# Medir-220-2.net
KiCad netlist of a schematic drawn in EAGLE
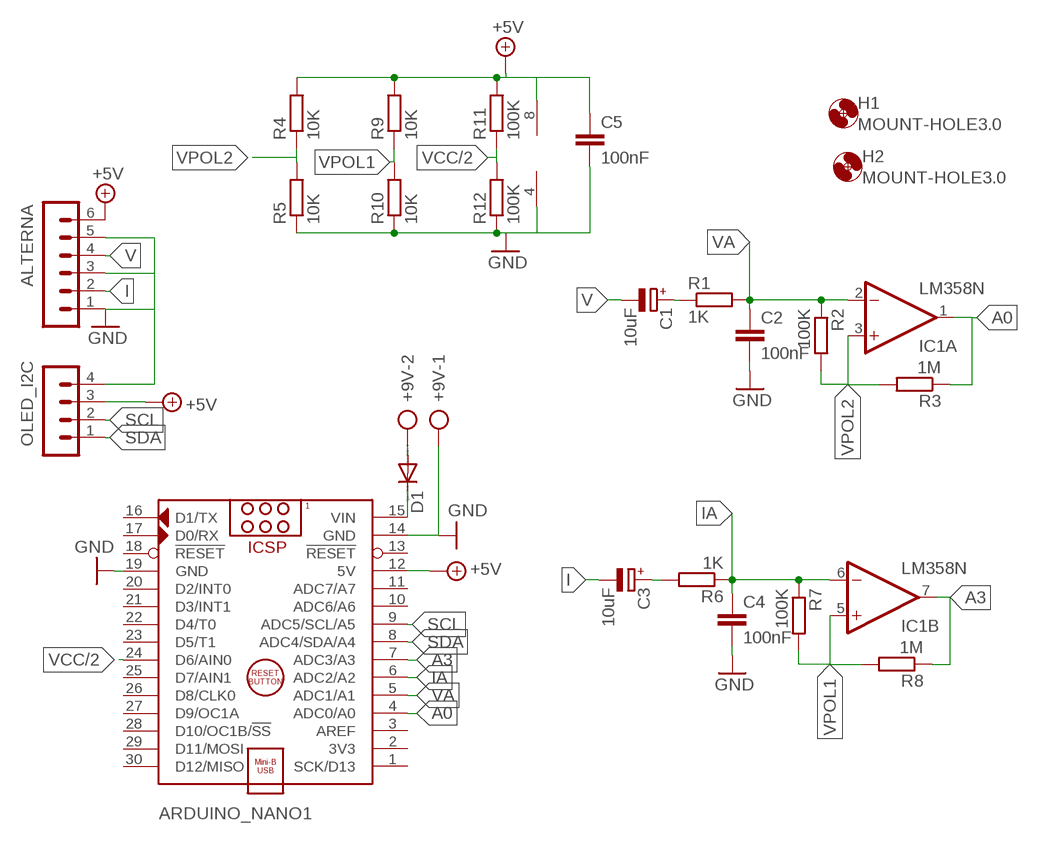
[diagram p0: schematic, sheet 1]

(export (version "E")
  (design (tool "Eeschema 10.0.6"))
  (components
    (comp (ref "+9V")
      (value "AK500/2")
      (footprint "eagle-import:AK500_2")
      (libsource (lib "eagle-import") (part "AK500/2"))
    )
    (comp (ref "ALTERNA")
      (value "MA06-1")
      (footprint "eagle-import:MA06-1")
      (libsource (lib "eagle-import") (part "MA06-1"))
    )
    (comp (ref "ARDUINO_NANO1")
      (value "ARDUINO_NANO")
      (footprint "eagle-import:ARDUINO_NANO")
      (libsource (lib "eagle-import") (part "ARDUINO_NANO"))
    )
    (comp (ref "C1")
      (value "10uF")
      (footprint "eagle-import:E2,5-5")
      (libsource (lib "eagle-import") (part "CPOL-EUE2.5-5"))
    )
    (comp (ref "C2")
      (value "100nF")
      (footprint "eagle-import:C050-025X075")
      (libsource (lib "eagle-import") (part "C-EU050-025X075"))
    )
    (comp (ref "C3")
      (value "10uF")
      (footprint "eagle-import:E2,5-5")
      (libsource (lib "eagle-import") (part "CPOL-EUE2.5-5"))
    )
    (comp (ref "C4")
      (value "100nF")
      (footprint "eagle-import:C050-025X075")
      (libsource (lib "eagle-import") (part "C-EU050-025X075"))
    )
    (comp (ref "C5")
      (value "100nF")
      (footprint "eagle-import:C025-025X050")
      (libsource (lib "eagle-import") (part "C-EU025-025X050"))
    )
    (comp (ref "D1")
      (value "DIODE-D-2.5")
      (footprint "eagle-import:D-2.5")
      (libsource (lib "eagle-import") (part "DIODE-D-2.5"))
    )
    (comp (ref "H1")
      (value "MOUNT-HOLE3.0")
      (footprint "eagle-import:3,0")
      (libsource (lib "eagle-import") (part "MOUNT-HOLE3.0"))
    )
    (comp (ref "H2")
      (value "MOUNT-HOLE3.0")
      (footprint "eagle-import:3,0")
      (libsource (lib "eagle-import") (part "MOUNT-HOLE3.0"))
    )
    (comp (ref "IC1")
      (value "LM358N")
      (footprint "eagle-import:DIL08")
      (libsource (lib "eagle-import") (part "LM358N"))
    )
    (comp (ref "OLED_I2C")
      (value "MA04-1")
      (footprint "eagle-import:MA04-1")
      (libsource (lib "eagle-import") (part "MA04-1"))
    )
    (comp (ref "R1")
      (value "1K")
      (footprint "eagle-import:0207_7")
      (libsource (lib "eagle-import") (part "R-EU_0207/7"))
    )
    (comp (ref "R2")
      (value "100K")
      (footprint "eagle-import:0207_7")
      (libsource (lib "eagle-import") (part "R-EU_0207/7"))
    )
    (comp (ref "R3")
      (value "1M")
      (footprint "eagle-import:0207_7")
      (libsource (lib "eagle-import") (part "R-EU_0207/7"))
    )
    (comp (ref "R4")
      (value "10K")
      (footprint "eagle-import:0207_10")
      (libsource (lib "eagle-import") (part "R-EU_0207/10"))
    )
    (comp (ref "R5")
      (value "10K")
      (footprint "eagle-import:0207_7")
      (libsource (lib "eagle-import") (part "R-EU_0207/7"))
    )
    (comp (ref "R6")
      (value "1K")
      (footprint "eagle-import:0207_7")
      (libsource (lib "eagle-import") (part "R-EU_0207/7"))
    )
    (comp (ref "R7")
      (value "100K")
      (footprint "eagle-import:0207_7")
      (libsource (lib "eagle-import") (part "R-EU_0207/7"))
    )
    (comp (ref "R8")
      (value "1M")
      (footprint "eagle-import:0207_7")
      (libsource (lib "eagle-import") (part "R-EU_0207/7"))
    )
    (comp (ref "R9")
      (value "10K")
      (footprint "eagle-import:0207_7")
      (libsource (lib "eagle-import") (part "R-EU_0207/7"))
    )
    (comp (ref "R10")
      (value "10K")
      (footprint "eagle-import:0207_7")
      (libsource (lib "eagle-import") (part "R-EU_0207/7"))
    )
    (comp (ref "R11")
      (value "100K")
      (footprint "eagle-import:0207_10")
      (libsource (lib "eagle-import") (part "R-EU_0207/10"))
    )
    (comp (ref "R12")
      (value "100K")
      (footprint "eagle-import:0207_10")
      (libsource (lib "eagle-import") (part "R-EU_0207/10"))
    )
  )
  (nets
    (net (code "1") (name "+5V") (class "Default")
      (node (ref "ALTERNA") (pin "6") (pinfunction "6_6") (pintype "passive"))
      (node (ref "ARDUINO_NANO1") (pin "12") (pinfunction "5V_12") (pintype "power_in"))
      (node (ref "C5") (pin "1") (pinfunction "1_1") (pintype "passive"))
      (node (ref "IC1") (pin "8") (pinfunction "V+_8") (pintype "power_in"))
      (node (ref "OLED_I2C") (pin "3") (pinfunction "3_3") (pintype "passive"))
      (node (ref "R11") (pin "2") (pinfunction "2_2") (pintype "passive"))
      (node (ref "R4") (pin "2") (pinfunction "2_2") (pintype "passive"))
      (node (ref "R9") (pin "2") (pinfunction "2_2") (pintype "passive"))
    )
    (net (code "2") (name "A0") (class "Default")
      (node (ref "ARDUINO_NANO1") (pin "4") (pinfunction "ADC0/A0_4") (pintype "bidirectional"))
      (node (ref "IC1") (pin "1") (pinfunction "OUT_1") (pintype "output"))
      (node (ref "R3") (pin "1") (pinfunction "1_1") (pintype "passive"))
    )
    (net (code "3") (name "A3") (class "Default")
      (node (ref "ARDUINO_NANO1") (pin "7") (pinfunction "ADC3/A3_7") (pintype "bidirectional"))
      (node (ref "IC1") (pin "7") (pinfunction "OUT_7") (pintype "output"))
      (node (ref "R8") (pin "1") (pinfunction "1_1") (pintype "passive"))
    )
    (net (code "4") (name "GND") (class "Default")
      (node (ref "+9V") (pin "1") (pinfunction "KL_1") (pintype "passive"))
      (node (ref "ALTERNA") (pin "1") (pinfunction "1_1") (pintype "passive"))
      (node (ref "ALTERNA") (pin "3") (pinfunction "3_3") (pintype "passive"))
      (node (ref "ALTERNA") (pin "5") (pinfunction "5_5") (pintype "passive"))
      (node (ref "ARDUINO_NANO1") (pin "14") (pinfunction "GND_14") (pintype "power_in"))
      (node (ref "ARDUINO_NANO1") (pin "19") (pinfunction "GND_19") (pintype "power_in"))
      (node (ref "C2") (pin "2") (pinfunction "2_2") (pintype "passive"))
      (node (ref "C4") (pin "2") (pinfunction "2_2") (pintype "passive"))
      (node (ref "C5") (pin "2") (pinfunction "2_2") (pintype "passive"))
      (node (ref "IC1") (pin "4") (pinfunction "V-_4") (pintype "power_in"))
      (node (ref "OLED_I2C") (pin "4") (pinfunction "4_4") (pintype "passive"))
      (node (ref "R10") (pin "1") (pinfunction "1_1") (pintype "passive"))
      (node (ref "R12") (pin "1") (pinfunction "1_1") (pintype "passive"))
      (node (ref "R5") (pin "1") (pinfunction "1_1") (pintype "passive"))
    )
    (net (code "5") (name "I") (class "Default")
      (node (ref "ALTERNA") (pin "2") (pinfunction "2_2") (pintype "passive"))
      (node (ref "C3") (pin "-") (pinfunction "-_-") (pintype "passive"))
    )
    (net (code "6") (name "IA") (class "Default")
      (node (ref "ARDUINO_NANO1") (pin "6") (pinfunction "ADC2/A2_6") (pintype "bidirectional"))
      (node (ref "C4") (pin "1") (pinfunction "1_1") (pintype "passive"))
      (node (ref "IC1") (pin "6") (pinfunction "-IN_6") (pintype "input"))
      (node (ref "R6") (pin "1") (pinfunction "1_1") (pintype "passive"))
      (node (ref "R7") (pin "1") (pinfunction "1_1") (pintype "passive"))
    )
    (net (code "7") (name "Net-(+9VB-KL)") (class "Default")
      (node (ref "+9V") (pin "2") (pinfunction "KL_2") (pintype "passive"))
      (node (ref "D1") (pin "A") (pinfunction "A_A") (pintype "passive"))
    )
    (net (code "8") (name "Net-(ARDUINO_NANO1-VIN)") (class "Default")
      (node (ref "ARDUINO_NANO1") (pin "15") (pinfunction "VIN_15") (pintype "power_in"))
      (node (ref "D1") (pin "C") (pinfunction "C_C") (pintype "passive"))
    )
    (net (code "9") (name "Net-(C1-Pad+)") (class "Default")
      (node (ref "C1") (pin "+") (pinfunction "+_+") (pintype "passive"))
      (node (ref "R1") (pin "1") (pinfunction "1_1") (pintype "passive"))
    )
    (net (code "10") (name "Net-(C3-Pad+)") (class "Default")
      (node (ref "C3") (pin "+") (pinfunction "+_+") (pintype "passive"))
      (node (ref "R6") (pin "2") (pinfunction "2_2") (pintype "passive"))
    )
    (net (code "11") (name "SCL") (class "Default")
      (node (ref "ARDUINO_NANO1") (pin "9") (pinfunction "ADC5/SCL/A5_9") (pintype "bidirectional"))
      (node (ref "OLED_I2C") (pin "2") (pinfunction "2_2") (pintype "passive"))
    )
    (net (code "12") (name "SDA") (class "Default")
      (node (ref "ARDUINO_NANO1") (pin "8") (pinfunction "ADC4/SDA/A4_8") (pintype "bidirectional"))
      (node (ref "OLED_I2C") (pin "1") (pinfunction "1_1") (pintype "passive"))
    )
    (net (code "13") (name "V") (class "Default")
      (node (ref "ALTERNA") (pin "4") (pinfunction "4_4") (pintype "passive"))
      (node (ref "C1") (pin "-") (pinfunction "-_-") (pintype "passive"))
    )
    (net (code "14") (name "VA") (class "Default")
      (node (ref "ARDUINO_NANO1") (pin "5") (pinfunction "ADC1/A1_5") (pintype "bidirectional"))
      (node (ref "C2") (pin "1") (pinfunction "1_1") (pintype "passive"))
      (node (ref "IC1") (pin "2") (pinfunction "-IN_2") (pintype "input"))
      (node (ref "R1") (pin "2") (pinfunction "2_2") (pintype "passive"))
      (node (ref "R2") (pin "1") (pinfunction "1_1") (pintype "passive"))
    )
    (net (code "15") (name "VCC{slash}2") (class "Default")
      (node (ref "ARDUINO_NANO1") (pin "24") (pinfunction "D6/AIN0_24") (pintype "bidirectional"))
      (node (ref "R11") (pin "1") (pinfunction "1_1") (pintype "passive"))
      (node (ref "R12") (pin "2") (pinfunction "2_2") (pintype "passive"))
    )
    (net (code "16") (name "VPOL1") (class "Default")
      (node (ref "IC1") (pin "5") (pinfunction "+IN_5") (pintype "input"))
      (node (ref "R10") (pin "2") (pinfunction "2_2") (pintype "passive"))
      (node (ref "R7") (pin "2") (pinfunction "2_2") (pintype "passive"))
      (node (ref "R8") (pin "2") (pinfunction "2_2") (pintype "passive"))
      (node (ref "R9") (pin "1") (pinfunction "1_1") (pintype "passive"))
    )
    (net (code "17") (name "VPOL2") (class "Default")
      (node (ref "IC1") (pin "3") (pinfunction "+IN_3") (pintype "input"))
      (node (ref "R2") (pin "2") (pinfunction "2_2") (pintype "passive"))
      (node (ref "R3") (pin "2") (pinfunction "2_2") (pintype "passive"))
      (node (ref "R4") (pin "1") (pinfunction "1_1") (pintype "passive"))
      (node (ref "R5") (pin "2") (pinfunction "2_2") (pintype "passive"))
    )
    (net (code "18") (name "unconnected-(ARDUINO_NANO1-3V3-Pad2)") (class "Default")
      (node (ref "ARDUINO_NANO1") (pin "2") (pinfunction "3V3_2") (pintype "output"))
    )
    (net (code "19") (name "unconnected-(ARDUINO_NANO1-ADC6{slash}A6-Pad10)") (class "Default")
      (node (ref "ARDUINO_NANO1") (pin "10") (pinfunction "ADC6/A6_10") (pintype "bidirectional"))
    )
    (net (code "20") (name "unconnected-(ARDUINO_NANO1-ADC7{slash}A7-Pad11)") (class "Default")
      (node (ref "ARDUINO_NANO1") (pin "11") (pinfunction "ADC7/A7_11") (pintype "bidirectional"))
    )
    (net (code "21") (name "unconnected-(ARDUINO_NANO1-AREF-Pad3)") (class "Default")
      (node (ref "ARDUINO_NANO1") (pin "3") (pinfunction "AREF_3") (pintype "input"))
    )
    (net (code "22") (name "unconnected-(ARDUINO_NANO1-D0{slash}RX-Pad17)") (class "Default")
      (node (ref "ARDUINO_NANO1") (pin "17") (pinfunction "D0/RX_17") (pintype "bidirectional"))
    )
    (net (code "23") (name "unconnected-(ARDUINO_NANO1-D1{slash}TX-Pad16)") (class "Default")
      (node (ref "ARDUINO_NANO1") (pin "16") (pinfunction "D1/TX_16") (pintype "bidirectional"))
    )
    (net (code "24") (name "unconnected-(ARDUINO_NANO1-D2{slash}INT0-Pad20)") (class "Default")
      (node (ref "ARDUINO_NANO1") (pin "20") (pinfunction "D2/INT0_20") (pintype "bidirectional"))
    )
    (net (code "25") (name "unconnected-(ARDUINO_NANO1-D3{slash}INT1-Pad21)") (class "Default")
      (node (ref "ARDUINO_NANO1") (pin "21") (pinfunction "D3/INT1_21") (pintype "bidirectional"))
    )
    (net (code "26") (name "unconnected-(ARDUINO_NANO1-D4{slash}T0-Pad22)") (class "Default")
      (node (ref "ARDUINO_NANO1") (pin "22") (pinfunction "D4/T0_22") (pintype "bidirectional"))
    )
    (net (code "27") (name "unconnected-(ARDUINO_NANO1-D5{slash}T1-Pad23)") (class "Default")
      (node (ref "ARDUINO_NANO1") (pin "23") (pinfunction "D5/T1_23") (pintype "bidirectional"))
    )
    (net (code "28") (name "unconnected-(ARDUINO_NANO1-D7{slash}AIN1-Pad25)") (class "Default")
      (node (ref "ARDUINO_NANO1") (pin "25") (pinfunction "D7/AIN1_25") (pintype "bidirectional"))
    )
    (net (code "29") (name "unconnected-(ARDUINO_NANO1-D8{slash}CLK0-Pad26)") (class "Default")
      (node (ref "ARDUINO_NANO1") (pin "26") (pinfunction "D8/CLK0_26") (pintype "bidirectional"))
    )
    (net (code "30") (name "unconnected-(ARDUINO_NANO1-D9{slash}OC1A-Pad27)") (class "Default")
      (node (ref "ARDUINO_NANO1") (pin "27") (pinfunction "D9/OC1A_27") (pintype "bidirectional"))
    )
    (net (code "31") (name "unconnected-(ARDUINO_NANO1-D10{slash}OC1B{slash}~{SS}-Pad28)") (class "Default")
      (node (ref "ARDUINO_NANO1") (pin "28") (pinfunction "D10/OC1B/~{SS}_28") (pintype "bidirectional"))
    )
    (net (code "32") (name "unconnected-(ARDUINO_NANO1-D11{slash}MOSI-Pad29)") (class "Default")
      (node (ref "ARDUINO_NANO1") (pin "29") (pinfunction "D11/MOSI_29") (pintype "bidirectional"))
    )
    (net (code "33") (name "unconnected-(ARDUINO_NANO1-D12{slash}MISO-Pad30)") (class "Default")
      (node (ref "ARDUINO_NANO1") (pin "30") (pinfunction "D12/MISO_30") (pintype "bidirectional"))
    )
    (net (code "34") (name "unconnected-(ARDUINO_NANO1-SCK{slash}D13-Pad1)") (class "Default")
      (node (ref "ARDUINO_NANO1") (pin "1") (pinfunction "SCK/D13_1") (pintype "bidirectional"))
    )
    (net (code "35") (name "unconnected-(ARDUINO_NANO1-~{RESET}-Pad13)") (class "Default")
      (node (ref "ARDUINO_NANO1") (pin "13") (pinfunction "~{RESET}_13") (pintype "input"))
    )
    (net (code "36") (name "unconnected-(ARDUINO_NANO1-~{RESET}-Pad18)") (class "Default")
      (node (ref "ARDUINO_NANO1") (pin "18") (pinfunction "~{RESET}_18") (pintype "input"))
    )
  )
)
